# 02_-_MCU.net
KiCad netlist of a schematic drawn in Altium Designer
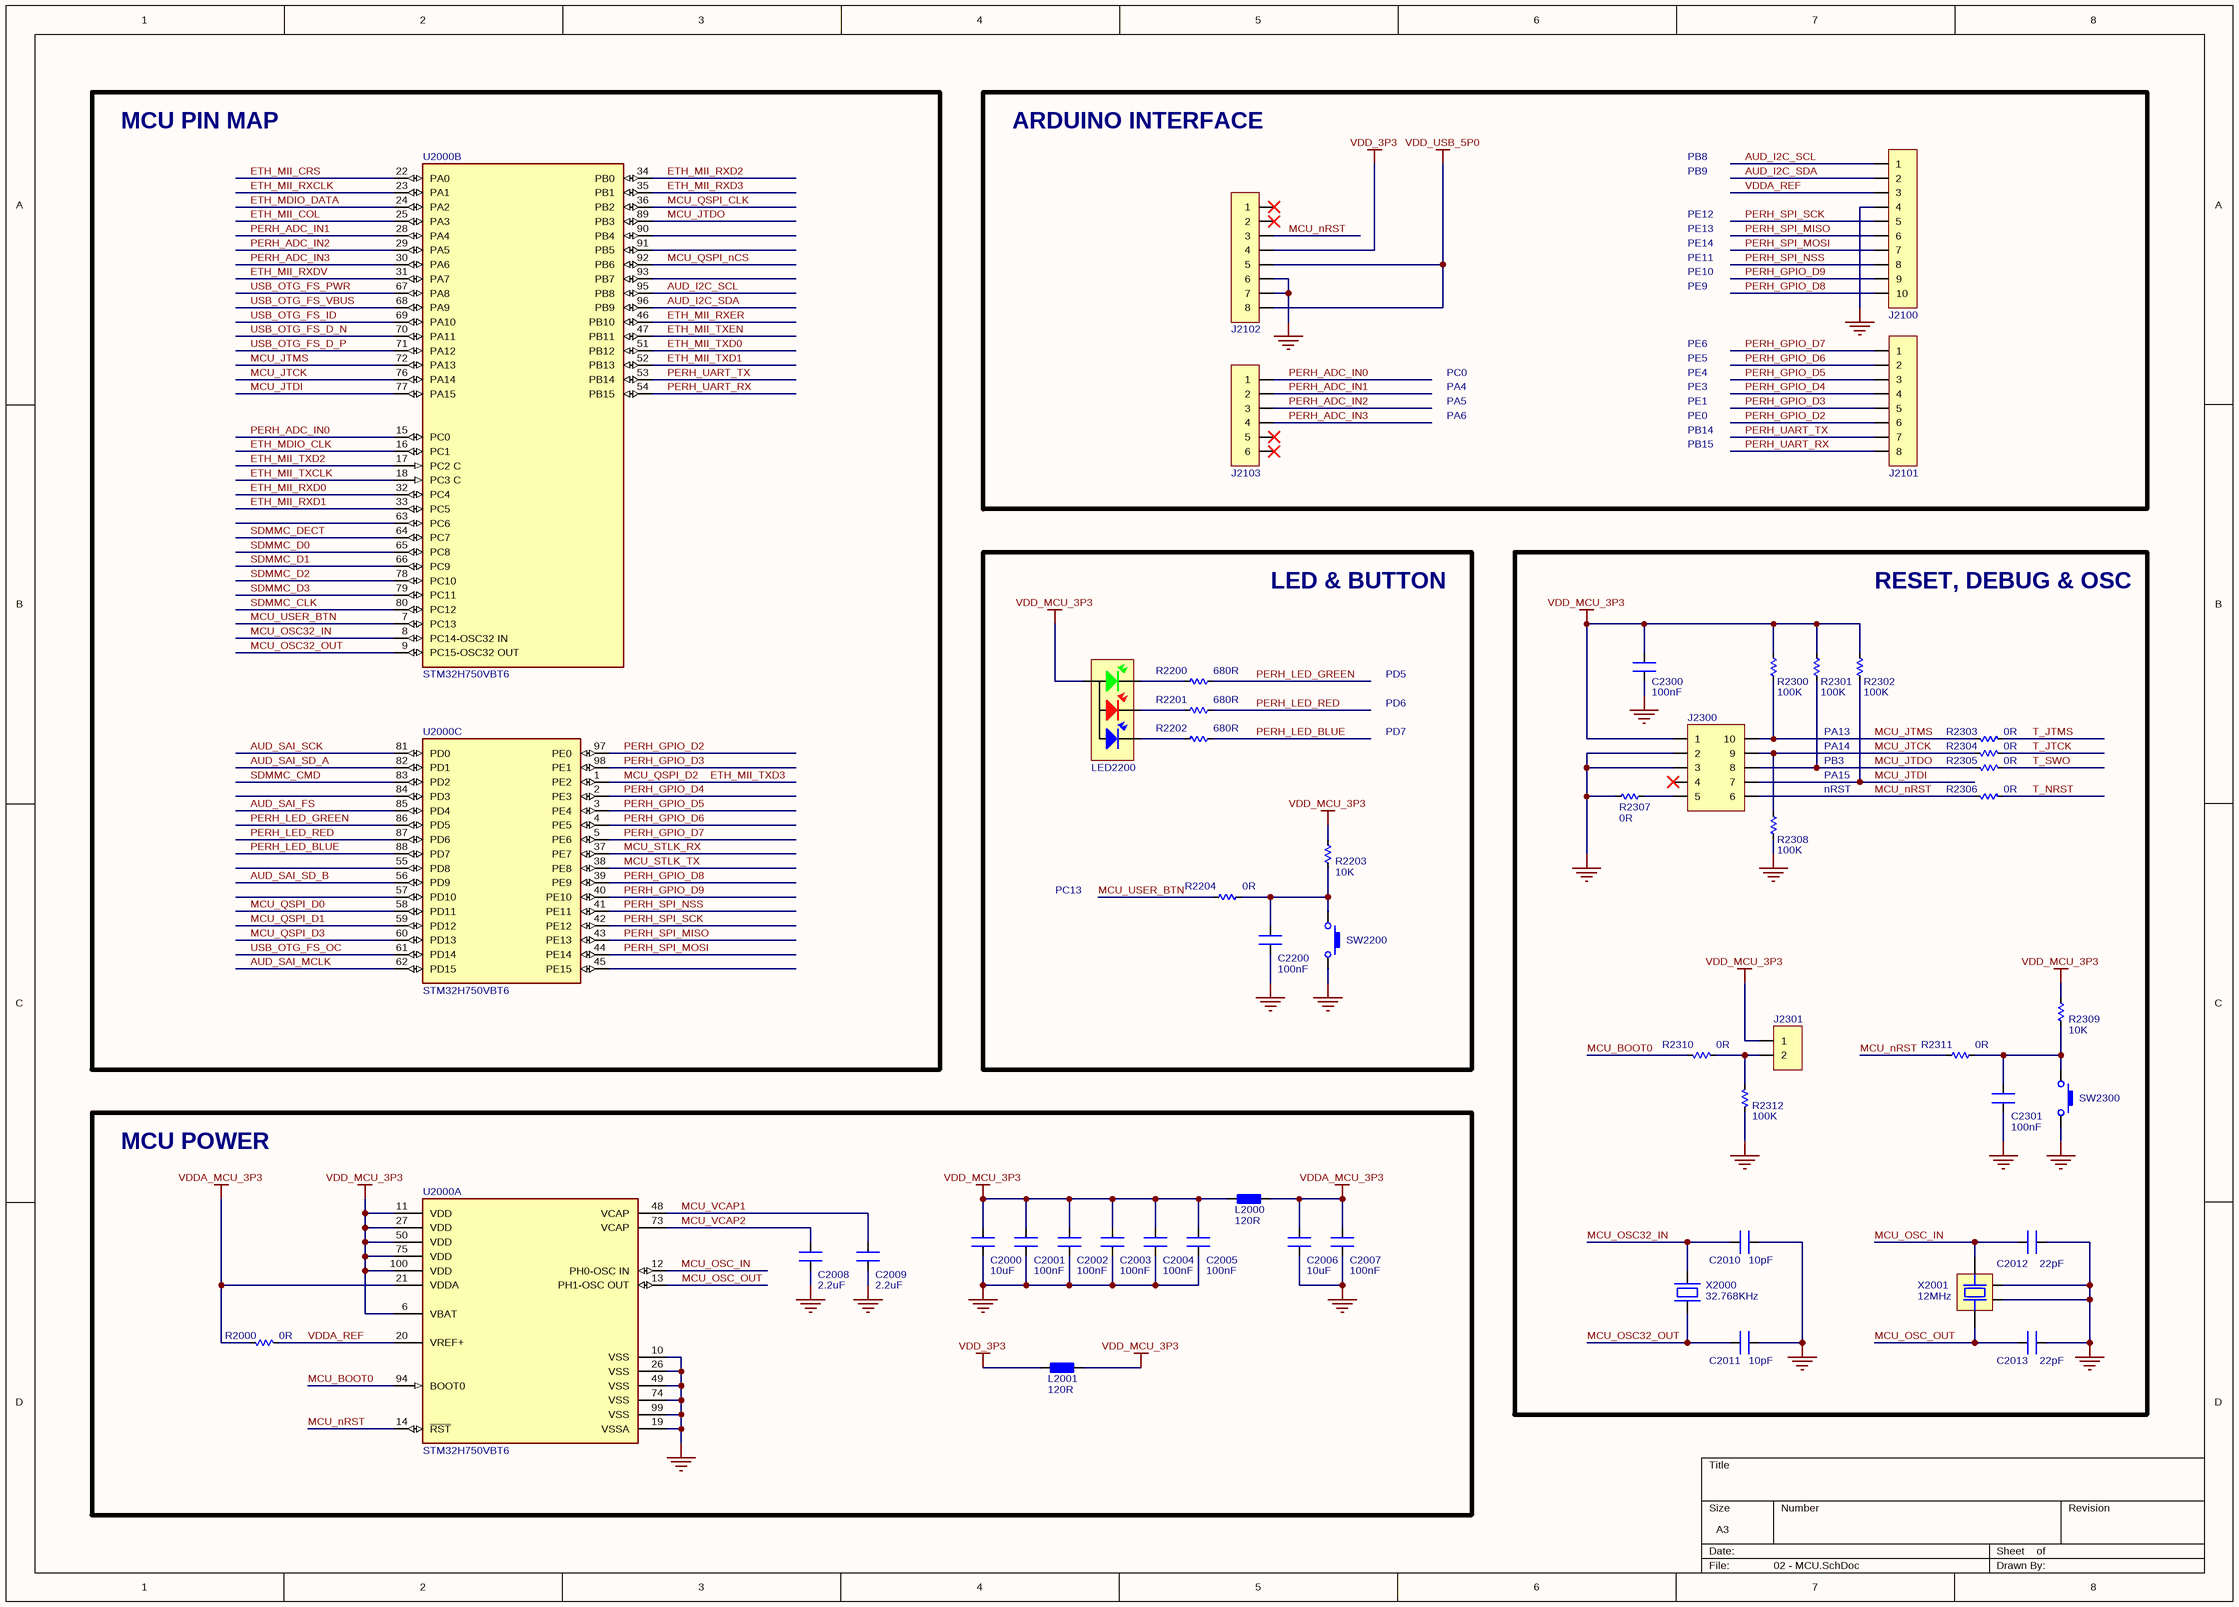
[diagram p0: 02 - MCU.SchDoc]

(export (version "E")
  (design (tool "Eeschema 10.0.6"))
  (components
    (comp (ref "C2000")
      (value "10uF")
      (footprint "CN-SMD-0603")
      (description "Ceramic Capacitor SMD 0603 10uF ±20% 10V")
      (fields (field (name "Comment") "Capacitor"))
      (libsource (lib "AS50") (part "Cap"))
    )
    (comp (ref "C2001")
      (value "100nF")
      (footprint "CN-SMD-0402")
      (description "Ceramic Capacitor SMD 0402 100nF ±20% 16V")
      (fields (field (name "Comment") "Capacitor"))
      (libsource (lib "AS50") (part "Cap"))
    )
    (comp (ref "C2002")
      (value "100nF")
      (footprint "CN-SMD-0402")
      (description "Ceramic Capacitor SMD 0402 100nF ±20% 16V")
      (fields (field (name "Comment") "Capacitor"))
      (libsource (lib "AS50") (part "Cap"))
    )
    (comp (ref "C2003")
      (value "100nF")
      (footprint "CN-SMD-0402")
      (description "Ceramic Capacitor SMD 0402 100nF ±20% 16V")
      (fields (field (name "Comment") "Capacitor"))
      (libsource (lib "AS50") (part "Cap"))
    )
    (comp (ref "C2004")
      (value "100nF")
      (footprint "CN-SMD-0402")
      (description "Ceramic Capacitor SMD 0402 100nF ±20% 16V")
      (fields (field (name "Comment") "Capacitor"))
      (libsource (lib "AS50") (part "Cap"))
    )
    (comp (ref "C2005")
      (value "100nF")
      (footprint "CN-SMD-0402")
      (description "Ceramic Capacitor SMD 0402 100nF ±20% 16V")
      (fields (field (name "Comment") "Capacitor"))
      (libsource (lib "AS50") (part "Cap"))
    )
    (comp (ref "C2006")
      (value "10uF")
      (footprint "CN-SMD-0603")
      (description "Ceramic Capacitor SMD 0603 10uF ±20% 10V")
      (fields (field (name "Comment") "Capacitor"))
      (libsource (lib "AS50") (part "Cap"))
    )
    (comp (ref "C2007")
      (value "100nF")
      (footprint "CN-SMD-0402")
      (description "Ceramic Capacitor SMD 0402 100nF ±20% 16V")
      (fields (field (name "Comment") "Capacitor"))
      (libsource (lib "AS50") (part "Cap"))
    )
    (comp (ref "C2008")
      (value "2.2uF")
      (footprint "CN-SMD-0603")
      (description "Ceramic Capacitor SMD 0603 2.2uF ±20% 16V")
      (fields (field (name "Comment") "Capacitor"))
      (libsource (lib "AS50") (part "Cap"))
    )
    (comp (ref "C2009")
      (value "2.2uF")
      (footprint "CN-SMD-0603")
      (description "Ceramic Capacitor SMD 0603 2.2uF ±20% 16V")
      (fields (field (name "Comment") "Capacitor"))
      (libsource (lib "AS50") (part "Cap"))
    )
    (comp (ref "C2010")
      (value "10pF")
      (footprint "CN-SMD-0402")
      (description "Ceramic Capacitor SMD 0402 10pF ±20% 50V")
      (fields (field (name "Comment") "Capacitor"))
      (libsource (lib "AS50") (part "Cap"))
    )
    (comp (ref "C2011")
      (value "10pF")
      (footprint "CN-SMD-0402")
      (description "Ceramic Capacitor SMD 0402 10pF ±20% 50V")
      (fields (field (name "Comment") "Capacitor"))
      (libsource (lib "AS50") (part "Cap"))
    )
    (comp (ref "C2012")
      (value "22pF")
      (footprint "CN-SMD-0402")
      (description "Ceramic Capacitor SMD 0402 22pF ±20% 50V")
      (fields (field (name "Comment") "Capacitor"))
      (libsource (lib "AS50") (part "Cap"))
    )
    (comp (ref "C2013")
      (value "22pF")
      (footprint "CN-SMD-0402")
      (description "Ceramic Capacitor SMD 0402 22pF ±20% 50V")
      (fields (field (name "Comment") "Capacitor"))
      (libsource (lib "AS50") (part "Cap"))
    )
    (comp (ref "C2200")
      (value "100nF")
      (footprint "CN-SMD-0402")
      (description "Ceramic Capacitor SMD 0402 100nF ±20% 16V")
      (fields (field (name "Comment") "Capacitor"))
      (libsource (lib "AS50") (part "Cap"))
    )
    (comp (ref "C2300")
      (value "100nF")
      (footprint "CN-SMD-0402")
      (description "Ceramic Capacitor SMD 0402 100nF ±20% 16V")
      (fields (field (name "Comment") "Capacitor"))
      (libsource (lib "AS50") (part "Cap"))
    )
    (comp (ref "C2301")
      (value "100nF")
      (footprint "CN-SMD-0402")
      (description "Ceramic Capacitor SMD 0402 100nF ±20% 16V")
      (fields (field (name "Comment") "Capacitor"))
      (libsource (lib "AS50") (part "Cap"))
    )
    (comp (ref "J2100")
      (value "Terminal strip")
      (footprint "JP10-C1T")
      (description "Terminal strip 10-pin 1-row pitch 0.1\" (2.54mm) DIP straight")
      (libsource (lib "AS50") (part "JP10"))
    )
    (comp (ref "J2101")
      (value "Terminal strip")
      (footprint "JP8-C1T")
      (description "Terminal strip 8-pin 1-row pitch 0.1\" (2.54mm) DIP straight")
      (libsource (lib "") (part "JP8_1"))
    )
    (comp (ref "J2102")
      (value "Terminal strip")
      (footprint "JP8-C1T")
      (description "Terminal strip 8-pin 1-row pitch 0.1\" (2.54mm) DIP straight")
      (libsource (lib "AS50") (part "JP8"))
    )
    (comp (ref "J2103")
      (value "Terminal strip")
      (footprint "JP6-C1T")
      (description "Terminal strip 6-pin 1-row pitch 0.1\" (2.54mm) DIP straight")
      (libsource (lib "AS50") (part "JP6"))
    )
    (comp (ref "J2300")
      (value "Terminal strip")
      (footprint "JP1.27-10P")
      (description "Terminal strip 5-pin 2-row pitch 0.05\" (1.27mm) SMD straight")
      (libsource (lib "AS50") (part "JP5x2"))
    )
    (comp (ref "J2301")
      (value "JP2")
      (footprint "JP2-D1T")
      (description "Single 2-pin jumper")
      (libsource (lib "AS50") (part "JP2"))
    )
    (comp (ref "L2000")
      (value "120R")
      (footprint "L-SMD-0402")
      (description "Ferrite bead SMD 0402 120 Ohm @100MHz")
      (fields (field (name "Comment") "Ferrite bead"))
      (libsource (lib "AS50") (part "Ferrite bead"))
    )
    (comp (ref "L2001")
      (value "120R")
      (footprint "L-SMD-0603")
      (description "Ferrite bead SMD 0603 120 Ohm @100MHz")
      (fields (field (name "Comment") "Ferrite bead"))
      (libsource (lib "AS50") (part "Ferrite bead"))
    )
    (comp (ref "LED2200")
      (value "LED")
      (footprint "LED-SMD-3528-RGB")
      (description "LED RGB Common Anode SMD-3528")
      (libsource (lib "AS50") (part "LED RGB CA"))
    )
    (comp (ref "R2000")
      (value "0R")
      (footprint "RES-SMD-0402")
      (description "Resistor SMD 0402 0R 1% 0.063W")
      (fields (field (name "Comment") "Resistor"))
      (libsource (lib "AS50") (part "Res"))
    )
    (comp (ref "R2200")
      (value "680R")
      (footprint "RES-SMD-0402")
      (description "Resistor SMD 0402 680R 1% 0.063W")
      (fields (field (name "Comment") "Resistor"))
      (libsource (lib "AS50") (part "Res"))
    )
    (comp (ref "R2201")
      (value "680R")
      (footprint "RES-SMD-0402")
      (description "Resistor SMD 0402 680R 1% 0.063W")
      (fields (field (name "Comment") "Resistor"))
      (libsource (lib "AS50") (part "Res"))
    )
    (comp (ref "R2202")
      (value "680R")
      (footprint "RES-SMD-0402")
      (description "Resistor SMD 0402 680R 1% 0.063W")
      (fields (field (name "Comment") "Resistor"))
      (libsource (lib "AS50") (part "Res"))
    )
    (comp (ref "R2203")
      (value "10K")
      (footprint "RES-SMD-0402")
      (description "Resistor SMD 0402 10K 1% 0.063W")
      (fields (field (name "Comment") "Resistor"))
      (libsource (lib "AS50") (part "Res"))
    )
    (comp (ref "R2204")
      (value "0R")
      (footprint "RES-SMD-0402")
      (description "Resistor SMD 0402 0R 1% 0.063W")
      (fields (field (name "Comment") "Resistor"))
      (libsource (lib "AS50") (part "Res"))
    )
    (comp (ref "R2300")
      (value "100K")
      (footprint "RES-SMD-0402")
      (description "Resistor SMD 0402 100K 1% 0.063W")
      (fields (field (name "Comment") "Resistor"))
      (libsource (lib "AS50") (part "Res"))
    )
    (comp (ref "R2301")
      (value "100K")
      (footprint "RES-SMD-0402")
      (description "Resistor SMD 0402 100K 1% 0.063W")
      (fields (field (name "Comment") "Resistor"))
      (libsource (lib "AS50") (part "Res"))
    )
    (comp (ref "R2302")
      (value "100K")
      (footprint "RES-SMD-0402")
      (description "Resistor SMD 0402 100K 1% 0.063W")
      (fields (field (name "Comment") "Resistor"))
      (libsource (lib "AS50") (part "Res"))
    )
    (comp (ref "R2303")
      (value "0R")
      (footprint "RES-SMD-0402")
      (description "Resistor SMD 0402 0R 1% 0.063W")
      (fields (field (name "Comment") "Resistor"))
      (libsource (lib "AS50") (part "Res"))
    )
    (comp (ref "R2304")
      (value "0R")
      (footprint "RES-SMD-0402")
      (description "Resistor SMD 0402 0R 1% 0.063W")
      (fields (field (name "Comment") "Resistor"))
      (libsource (lib "AS50") (part "Res"))
    )
    (comp (ref "R2305")
      (value "0R")
      (footprint "RES-SMD-0402")
      (description "Resistor SMD 0402 0R 1% 0.063W")
      (fields (field (name "Comment") "Resistor"))
      (libsource (lib "AS50") (part "Res"))
    )
    (comp (ref "R2306")
      (value "0R")
      (footprint "RES-SMD-0402")
      (description "Resistor SMD 0402 0R 1% 0.063W")
      (fields (field (name "Comment") "Resistor"))
      (libsource (lib "AS50") (part "Res"))
    )
    (comp (ref "R2307")
      (value "0R")
      (footprint "RES-SMD-0402")
      (description "Resistor SMD 0402 0R 1% 0.063W")
      (fields (field (name "Comment") "Resistor"))
      (libsource (lib "AS50") (part "Res"))
    )
    (comp (ref "R2308")
      (value "100K")
      (footprint "RES-SMD-0402")
      (description "Resistor SMD 0402 100K 1% 0.063W")
      (fields (field (name "Comment") "Resistor"))
      (libsource (lib "AS50") (part "Res"))
    )
    (comp (ref "R2309")
      (value "10K")
      (footprint "RES-SMD-0402")
      (description "Resistor SMD 0402 10K 1% 0.063W")
      (fields (field (name "Comment") "Resistor"))
      (libsource (lib "AS50") (part "Res"))
    )
    (comp (ref "R2310")
      (value "0R")
      (footprint "RES-SMD-0402")
      (description "Resistor SMD 0402 0R 1% 0.063W")
      (fields (field (name "Comment") "Resistor"))
      (libsource (lib "AS50") (part "Res"))
    )
    (comp (ref "R2311")
      (value "0R")
      (footprint "RES-SMD-0402")
      (description "Resistor SMD 0402 0R 1% 0.063W")
      (fields (field (name "Comment") "Resistor"))
      (libsource (lib "AS50") (part "Res"))
    )
    (comp (ref "R2312")
      (value "100K")
      (footprint "RES-SMD-0402")
      (description "Resistor SMD 0402 100K 1% 0.063W")
      (fields (field (name "Comment") "Resistor"))
      (libsource (lib "AS50") (part "Res"))
    )
    (comp (ref "SW2200")
      (value "Switch")
      (footprint "SW2-SMD-3x4x2M")
      (description "Tackle Switch 2-pin SMD 3x4x2mm")
      (libsource (lib "AS50") (part "SW2"))
    )
    (comp (ref "SW2300")
      (value "Switch")
      (footprint "SW2-SMD-3x4x2M")
      (description "Tackle Switch 2-pin SMD 3x4x2mm")
      (libsource (lib "AS50") (part "SW2"))
    )
    (comp (ref "U2000")
      (value "STM32H750VBT6")
      (footprint "FP-LQFP100-1L-IPC_B")
      (fields
        (field (name "OCTOPART") "https://octopart.com/stm32h750vbt6-stmicroelectronics-94048547")
        (field (name "MANUFACTURER") "STMicroelectronics")
      )
      (libsource (lib "Altium Content Vault") (part "aca449acb2b80670ba40d015d68dc7a"))
    )
    (comp (ref "X2000")
      (value "32.768KHz")
      (footprint "XT-SMD-FC-135")
      (description "Crystal Oscillator FC-135 32.768KHz 2-pin")
      (fields (field (name "Comment") "Crystal"))
      (libsource (lib "AS50") (part "XT2"))
    )
    (comp (ref "X2001")
      (value "12MHz")
      (footprint "XT-SMD-3225-4P")
      (description "Crystal Oscillator SMD-3225 12MHz 4-pin")
      (fields (field (name "Comment") "Crystal"))
      (libsource (lib "AS50") (part "XT4"))
    )
  )
  (nets
    (net (code "1") (name "/AUD_I2C_SCL") (class "Default")
      (node (ref "J2100") (pin "1") (pinfunction "1_1") (pintype "passive"))
      (node (ref "U2000") (pin "95") (pinfunction "PB8_95") (pintype "bidirectional"))
    )
    (net (code "2") (name "/AUD_I2C_SDA") (class "Default")
      (node (ref "J2100") (pin "2") (pinfunction "2_2") (pintype "passive"))
      (node (ref "U2000") (pin "96") (pinfunction "PB9_96") (pintype "bidirectional"))
    )
    (net (code "3") (name "/AUD_SAI_FS") (class "Default")
      (node (ref "U2000") (pin "85") (pinfunction "PD4_85") (pintype "bidirectional"))
    )
    (net (code "4") (name "/AUD_SAI_MCLK") (class "Default")
      (node (ref "U2000") (pin "62") (pinfunction "PD15_62") (pintype "bidirectional"))
    )
    (net (code "5") (name "/AUD_SAI_SCK") (class "Default")
      (node (ref "U2000") (pin "81") (pinfunction "PD0_81") (pintype "bidirectional"))
    )
    (net (code "6") (name "/AUD_SAI_SD_A") (class "Default")
      (node (ref "U2000") (pin "82") (pinfunction "PD1_82") (pintype "bidirectional"))
    )
    (net (code "7") (name "/AUD_SAI_SD_B") (class "Default")
      (node (ref "U2000") (pin "56") (pinfunction "PD9_56") (pintype "bidirectional"))
    )
    (net (code "8") (name "/ETH_MDIO_CLK") (class "Default")
      (node (ref "U2000") (pin "16") (pinfunction "PC1_16") (pintype "bidirectional"))
    )
    (net (code "9") (name "/ETH_MDIO_DATA") (class "Default")
      (node (ref "U2000") (pin "24") (pinfunction "PA2_24") (pintype "bidirectional"))
    )
    (net (code "10") (name "/ETH_MII_COL") (class "Default")
      (node (ref "U2000") (pin "25") (pinfunction "PA3_25") (pintype "bidirectional"))
    )
    (net (code "11") (name "/ETH_MII_CRS") (class "Default")
      (node (ref "U2000") (pin "22") (pinfunction "PA0_22") (pintype "bidirectional"))
    )
    (net (code "12") (name "/ETH_MII_RXCLK") (class "Default")
      (node (ref "U2000") (pin "23") (pinfunction "PA1_23") (pintype "bidirectional"))
    )
    (net (code "13") (name "/ETH_MII_RXD0") (class "Default")
      (node (ref "U2000") (pin "32") (pinfunction "PC4_32") (pintype "bidirectional"))
    )
    (net (code "14") (name "/ETH_MII_RXD1") (class "Default")
      (node (ref "U2000") (pin "33") (pinfunction "PC5_33") (pintype "bidirectional"))
    )
    (net (code "15") (name "/ETH_MII_RXD2") (class "Default")
      (node (ref "U2000") (pin "34") (pinfunction "PB0_34") (pintype "bidirectional"))
    )
    (net (code "16") (name "/ETH_MII_RXD3") (class "Default")
      (node (ref "U2000") (pin "35") (pinfunction "PB1_35") (pintype "bidirectional"))
    )
    (net (code "17") (name "/ETH_MII_RXDV") (class "Default")
      (node (ref "U2000") (pin "31") (pinfunction "PA7_31") (pintype "bidirectional"))
    )
    (net (code "18") (name "/ETH_MII_RXER") (class "Default")
      (node (ref "U2000") (pin "46") (pinfunction "PB10_46") (pintype "bidirectional"))
    )
    (net (code "19") (name "/ETH_MII_TXCLK") (class "Default")
      (node (ref "U2000") (pin "18") (pinfunction "PC3_C_18") (pintype "input"))
    )
    (net (code "20") (name "/ETH_MII_TXD0") (class "Default")
      (node (ref "U2000") (pin "51") (pinfunction "PB12_51") (pintype "bidirectional"))
    )
    (net (code "21") (name "/ETH_MII_TXD1") (class "Default")
      (node (ref "U2000") (pin "52") (pinfunction "PB13_52") (pintype "bidirectional"))
    )
    (net (code "22") (name "/ETH_MII_TXD2") (class "Default")
      (node (ref "U2000") (pin "17") (pinfunction "PC2_C_17") (pintype "input"))
    )
    (net (code "23") (name "/ETH_MII_TXD3") (class "Default")
      (node (ref "U2000") (pin "1") (pinfunction "PE2_1") (pintype "bidirectional"))
    )
    (net (code "24") (name "/ETH_MII_TXEN") (class "Default")
      (node (ref "U2000") (pin "47") (pinfunction "PB11_47") (pintype "bidirectional"))
    )
    (net (code "25") (name "/MCU_BOOT0") (class "Default")
      (node (ref "R2310") (pin "2") (pinfunction "2_2") (pintype "passive"))
      (node (ref "U2000") (pin "94") (pinfunction "BOOT0_94") (pintype "input"))
    )
    (net (code "26") (name "/MCU_JTCK") (class "Default")
      (node (ref "J2300") (pin "9") (pinfunction "9_9") (pintype "passive"))
      (node (ref "R2304") (pin "2") (pinfunction "2_2") (pintype "passive"))
      (node (ref "R2308") (pin "1") (pinfunction "1_1") (pintype "passive"))
      (node (ref "U2000") (pin "76") (pinfunction "PA14_76") (pintype "bidirectional"))
    )
    (net (code "27") (name "/MCU_JTDI") (class "Default")
      (node (ref "J2300") (pin "7") (pinfunction "7_7") (pintype "passive"))
      (node (ref "R2302") (pin "2") (pinfunction "2_2") (pintype "passive"))
      (node (ref "U2000") (pin "77") (pinfunction "PA15_77") (pintype "bidirectional"))
    )
    (net (code "28") (name "/MCU_JTDO") (class "Default")
      (node (ref "J2300") (pin "8") (pinfunction "8_8") (pintype "passive"))
      (node (ref "R2301") (pin "2") (pinfunction "2_2") (pintype "passive"))
      (node (ref "R2305") (pin "2") (pinfunction "2_2") (pintype "passive"))
      (node (ref "U2000") (pin "89") (pinfunction "PB3_89") (pintype "bidirectional"))
    )
    (net (code "29") (name "/MCU_JTMS") (class "Default")
      (node (ref "J2300") (pin "10") (pinfunction "10_10") (pintype "passive"))
      (node (ref "R2300") (pin "2") (pinfunction "2_2") (pintype "passive"))
      (node (ref "R2303") (pin "2") (pinfunction "2_2") (pintype "passive"))
      (node (ref "U2000") (pin "72") (pinfunction "PA13_72") (pintype "bidirectional"))
    )
    (net (code "30") (name "/MCU_OSC32_IN") (class "Default")
      (node (ref "C2010") (pin "2") (pinfunction "2_2") (pintype "passive"))
      (node (ref "U2000") (pin "8") (pinfunction "PC14-OSC32_IN_8") (pintype "bidirectional"))
      (node (ref "X2000") (pin "2") (pinfunction "2_2") (pintype "passive"))
    )
    (net (code "31") (name "/MCU_OSC32_OUT") (class "Default")
      (node (ref "C2011") (pin "2") (pinfunction "2_2") (pintype "passive"))
      (node (ref "U2000") (pin "9") (pinfunction "PC15-OSC32_OUT_9") (pintype "bidirectional"))
      (node (ref "X2000") (pin "1") (pinfunction "1_1") (pintype "passive"))
    )
    (net (code "32") (name "/MCU_OSC_IN") (class "Default")
      (node (ref "C2012") (pin "1") (pinfunction "1_1") (pintype "passive"))
      (node (ref "U2000") (pin "12") (pinfunction "PH0-OSC_IN_12") (pintype "bidirectional"))
      (node (ref "X2001") (pin "3") (pinfunction "3_3") (pintype "passive"))
    )
    (net (code "33") (name "/MCU_OSC_OUT") (class "Default")
      (node (ref "C2013") (pin "1") (pinfunction "1_1") (pintype "passive"))
      (node (ref "U2000") (pin "13") (pinfunction "PH1-OSC_OUT_13") (pintype "bidirectional"))
      (node (ref "X2001") (pin "1") (pinfunction "1_1") (pintype "passive"))
    )
    (net (code "34") (name "/MCU_QSPI_CLK") (class "Default")
      (node (ref "U2000") (pin "36") (pinfunction "PB2_36") (pintype "bidirectional"))
    )
    (net (code "35") (name "/MCU_QSPI_D0") (class "Default")
      (node (ref "U2000") (pin "58") (pinfunction "PD11_58") (pintype "bidirectional"))
    )
    (net (code "36") (name "/MCU_QSPI_D1") (class "Default")
      (node (ref "U2000") (pin "59") (pinfunction "PD12_59") (pintype "bidirectional"))
    )
    (net (code "37") (name "/MCU_QSPI_D3") (class "Default")
      (node (ref "U2000") (pin "60") (pinfunction "PD13_60") (pintype "bidirectional"))
    )
    (net (code "38") (name "/MCU_QSPI_nCS") (class "Default")
      (node (ref "U2000") (pin "92") (pinfunction "PB6_92") (pintype "bidirectional"))
    )
    (net (code "39") (name "/MCU_STLK_RX") (class "Default")
      (node (ref "U2000") (pin "37") (pinfunction "PE7_37") (pintype "bidirectional"))
    )
    (net (code "40") (name "/MCU_STLK_TX") (class "Default")
      (node (ref "U2000") (pin "38") (pinfunction "PE8_38") (pintype "bidirectional"))
    )
    (net (code "41") (name "/MCU_USER_BTN") (class "Default")
      (node (ref "R2204") (pin "1") (pinfunction "1_1") (pintype "passive"))
      (node (ref "U2000") (pin "7") (pinfunction "PC13_7") (pintype "bidirectional"))
    )
    (net (code "42") (name "/MCU_VCAP1") (class "Default")
      (node (ref "C2009") (pin "2") (pinfunction "2_2") (pintype "passive"))
      (node (ref "U2000") (pin "48") (pinfunction "VCAP_48") (pintype "power_in"))
    )
    (net (code "43") (name "/MCU_VCAP2") (class "Default")
      (node (ref "C2008") (pin "2") (pinfunction "2_2") (pintype "passive"))
      (node (ref "U2000") (pin "73") (pinfunction "VCAP_73") (pintype "power_in"))
    )
    (net (code "44") (name "/MCU_nRST") (class "Default")
      (node (ref "J2102") (pin "3") (pinfunction "3_3") (pintype "passive"))
      (node (ref "J2300") (pin "6") (pinfunction "6_6") (pintype "passive"))
      (node (ref "R2306") (pin "2") (pinfunction "2_2") (pintype "passive"))
      (node (ref "R2311") (pin "1") (pinfunction "1_1") (pintype "passive"))
      (node (ref "U2000") (pin "14") (pinfunction "~{RST}_14") (pintype "bidirectional"))
    )
    (net (code "45") (name "/PERH_ADC_IN0") (class "Default")
      (node (ref "J2103") (pin "1") (pinfunction "1_1") (pintype "passive"))
      (node (ref "U2000") (pin "15") (pinfunction "PC0_15") (pintype "bidirectional"))
    )
    (net (code "46") (name "/PERH_ADC_IN1") (class "Default")
      (node (ref "J2103") (pin "2") (pinfunction "2_2") (pintype "passive"))
      (node (ref "U2000") (pin "28") (pinfunction "PA4_28") (pintype "bidirectional"))
    )
    (net (code "47") (name "/PERH_ADC_IN2") (class "Default")
      (node (ref "J2103") (pin "3") (pinfunction "3_3") (pintype "passive"))
      (node (ref "U2000") (pin "29") (pinfunction "PA5_29") (pintype "bidirectional"))
    )
    (net (code "48") (name "/PERH_ADC_IN3") (class "Default")
      (node (ref "J2103") (pin "4") (pinfunction "4_4") (pintype "passive"))
      (node (ref "U2000") (pin "30") (pinfunction "PA6_30") (pintype "bidirectional"))
    )
    (net (code "49") (name "/PERH_GPIO_D2") (class "Default")
      (node (ref "J2101") (pin "6") (pinfunction "6_6") (pintype "passive"))
      (node (ref "U2000") (pin "97") (pinfunction "PE0_97") (pintype "bidirectional"))
    )
    (net (code "50") (name "/PERH_GPIO_D3") (class "Default")
      (node (ref "J2101") (pin "5") (pinfunction "5_5") (pintype "passive"))
      (node (ref "U2000") (pin "98") (pinfunction "PE1_98") (pintype "bidirectional"))
    )
    (net (code "51") (name "/PERH_GPIO_D4") (class "Default")
      (node (ref "J2101") (pin "4") (pinfunction "4_4") (pintype "passive"))
      (node (ref "U2000") (pin "2") (pinfunction "PE3_2") (pintype "bidirectional"))
    )
    (net (code "52") (name "/PERH_GPIO_D5") (class "Default")
      (node (ref "J2101") (pin "3") (pinfunction "3_3") (pintype "passive"))
      (node (ref "U2000") (pin "3") (pinfunction "PE4_3") (pintype "bidirectional"))
    )
    (net (code "53") (name "/PERH_GPIO_D6") (class "Default")
      (node (ref "J2101") (pin "2") (pinfunction "2_2") (pintype "passive"))
      (node (ref "U2000") (pin "4") (pinfunction "PE5_4") (pintype "bidirectional"))
    )
    (net (code "54") (name "/PERH_GPIO_D7") (class "Default")
      (node (ref "J2101") (pin "1") (pinfunction "1_1") (pintype "passive"))
      (node (ref "U2000") (pin "5") (pinfunction "PE6_5") (pintype "bidirectional"))
    )
    (net (code "55") (name "/PERH_GPIO_D8") (class "Default")
      (node (ref "J2100") (pin "10") (pinfunction "10_10") (pintype "passive"))
      (node (ref "U2000") (pin "39") (pinfunction "PE9_39") (pintype "bidirectional"))
    )
    (net (code "56") (name "/PERH_GPIO_D9") (class "Default")
      (node (ref "J2100") (pin "9") (pinfunction "9_9") (pintype "passive"))
      (node (ref "U2000") (pin "40") (pinfunction "PE10_40") (pintype "bidirectional"))
    )
    (net (code "57") (name "/PERH_LED_BLUE") (class "Default")
      (node (ref "R2202") (pin "2") (pinfunction "2_2") (pintype "passive"))
      (node (ref "U2000") (pin "88") (pinfunction "PD7_88") (pintype "bidirectional"))
    )
    (net (code "58") (name "/PERH_LED_GREEN") (class "Default")
      (node (ref "R2200") (pin "2") (pinfunction "2_2") (pintype "passive"))
      (node (ref "U2000") (pin "86") (pinfunction "PD5_86") (pintype "bidirectional"))
    )
    (net (code "59") (name "/PERH_LED_RED") (class "Default")
      (node (ref "R2201") (pin "2") (pinfunction "2_2") (pintype "passive"))
      (node (ref "U2000") (pin "87") (pinfunction "PD6_87") (pintype "bidirectional"))
    )
    (net (code "60") (name "/PERH_SPI_MISO") (class "Default")
      (node (ref "J2100") (pin "6") (pinfunction "6_6") (pintype "passive"))
      (node (ref "U2000") (pin "43") (pinfunction "PE13_43") (pintype "bidirectional"))
    )
    (net (code "61") (name "/PERH_SPI_MOSI") (class "Default")
      (node (ref "J2100") (pin "7") (pinfunction "7_7") (pintype "passive"))
      (node (ref "U2000") (pin "44") (pinfunction "PE14_44") (pintype "bidirectional"))
    )
    (net (code "62") (name "/PERH_SPI_NSS") (class "Default")
      (node (ref "J2100") (pin "8") (pinfunction "8_8") (pintype "passive"))
      (node (ref "U2000") (pin "41") (pinfunction "PE11_41") (pintype "bidirectional"))
    )
    (net (code "63") (name "/PERH_SPI_SCK") (class "Default")
      (node (ref "J2100") (pin "5") (pinfunction "5_5") (pintype "passive"))
      (node (ref "U2000") (pin "42") (pinfunction "PE12_42") (pintype "bidirectional"))
    )
    (net (code "64") (name "/PERH_UART_RX") (class "Default")
      (node (ref "J2101") (pin "8") (pinfunction "8_8") (pintype "passive"))
      (node (ref "U2000") (pin "54") (pinfunction "PB15_54") (pintype "bidirectional"))
    )
    (net (code "65") (name "/PERH_UART_TX") (class "Default")
      (node (ref "J2101") (pin "7") (pinfunction "7_7") (pintype "passive"))
      (node (ref "U2000") (pin "53") (pinfunction "PB14_53") (pintype "bidirectional"))
    )
    (net (code "66") (name "/SDMMC_CLK") (class "Default")
      (node (ref "U2000") (pin "80") (pinfunction "PC12_80") (pintype "bidirectional"))
    )
    (net (code "67") (name "/SDMMC_CMD") (class "Default")
      (node (ref "U2000") (pin "83") (pinfunction "PD2_83") (pintype "bidirectional"))
    )
    (net (code "68") (name "/SDMMC_D0") (class "Default")
      (node (ref "U2000") (pin "65") (pinfunction "PC8_65") (pintype "bidirectional"))
    )
    (net (code "69") (name "/SDMMC_D1") (class "Default")
      (node (ref "U2000") (pin "66") (pinfunction "PC9_66") (pintype "bidirectional"))
    )
    (net (code "70") (name "/SDMMC_D2") (class "Default")
      (node (ref "U2000") (pin "78") (pinfunction "PC10_78") (pintype "bidirectional"))
    )
    (net (code "71") (name "/SDMMC_D3") (class "Default")
      (node (ref "U2000") (pin "79") (pinfunction "PC11_79") (pintype "bidirectional"))
    )
    (net (code "72") (name "/SDMMC_DECT") (class "Default")
      (node (ref "U2000") (pin "64") (pinfunction "PC7_64") (pintype "bidirectional"))
    )
    (net (code "73") (name "/T_JTCK") (class "Default")
      (node (ref "R2304") (pin "1") (pinfunction "1_1") (pintype "passive"))
    )
    (net (code "74") (name "/T_JTMS") (class "Default")
      (node (ref "R2303") (pin "1") (pinfunction "1_1") (pintype "passive"))
    )
    (net (code "75") (name "/T_NRST") (class "Default")
      (node (ref "R2306") (pin "1") (pinfunction "1_1") (pintype "passive"))
    )
    (net (code "76") (name "/T_SWO") (class "Default")
      (node (ref "R2305") (pin "1") (pinfunction "1_1") (pintype "passive"))
    )
    (net (code "77") (name "/USB_OTG_FS_D_N") (class "Default")
      (node (ref "U2000") (pin "70") (pinfunction "PA11_70") (pintype "bidirectional"))
    )
    (net (code "78") (name "/USB_OTG_FS_D_P") (class "Default")
      (node (ref "U2000") (pin "71") (pinfunction "PA12_71") (pintype "bidirectional"))
    )
    (net (code "79") (name "/USB_OTG_FS_ID") (class "Default")
      (node (ref "U2000") (pin "69") (pinfunction "PA10_69") (pintype "bidirectional"))
    )
    (net (code "80") (name "/USB_OTG_FS_OC") (class "Default")
      (node (ref "U2000") (pin "61") (pinfunction "PD14_61") (pintype "bidirectional"))
    )
    (net (code "81") (name "/USB_OTG_FS_PWR") (class "Default")
      (node (ref "U2000") (pin "67") (pinfunction "PA8_67") (pintype "bidirectional"))
    )
    (net (code "82") (name "/USB_OTG_FS_VBUS") (class "Default")
      (node (ref "U2000") (pin "68") (pinfunction "PA9_68") (pintype "bidirectional"))
    )
    (net (code "83") (name "/VDDA_REF") (class "Default")
      (node (ref "J2100") (pin "3") (pinfunction "3_3") (pintype "passive"))
      (node (ref "R2000") (pin "1") (pinfunction "1_1") (pintype "passive"))
      (node (ref "U2000") (pin "20") (pinfunction "VREF+_20") (pintype "power_in"))
    )
    (net (code "84") (name "GND") (class "Default")
      (node (ref "C2000") (pin "1") (pinfunction "1_1") (pintype "passive"))
      (node (ref "C2001") (pin "1") (pinfunction "1_1") (pintype "passive"))
      (node (ref "C2002") (pin "1") (pinfunction "1_1") (pintype "passive"))
      (node (ref "C2003") (pin "1") (pinfunction "1_1") (pintype "passive"))
      (node (ref "C2004") (pin "1") (pinfunction "1_1") (pintype "passive"))
      (node (ref "C2005") (pin "1") (pinfunction "1_1") (pintype "passive"))
      (node (ref "C2006") (pin "1") (pinfunction "1_1") (pintype "passive"))
      (node (ref "C2007") (pin "1") (pinfunction "1_1") (pintype "passive"))
      (node (ref "C2008") (pin "1") (pinfunction "1_1") (pintype "passive"))
      (node (ref "C2009") (pin "1") (pinfunction "1_1") (pintype "passive"))
      (node (ref "C2010") (pin "1") (pinfunction "1_1") (pintype "passive"))
      (node (ref "C2011") (pin "1") (pinfunction "1_1") (pintype "passive"))
      (node (ref "C2012") (pin "2") (pinfunction "2_2") (pintype "passive"))
      (node (ref "C2013") (pin "2") (pinfunction "2_2") (pintype "passive"))
      (node (ref "C2200") (pin "1") (pinfunction "1_1") (pintype "passive"))
      (node (ref "C2300") (pin "1") (pinfunction "1_1") (pintype "passive"))
      (node (ref "C2301") (pin "1") (pinfunction "1_1") (pintype "passive"))
      (node (ref "J2100") (pin "4") (pinfunction "4_4") (pintype "passive"))
      (node (ref "J2102") (pin "6") (pinfunction "6_6") (pintype "passive"))
      (node (ref "J2102") (pin "7") (pinfunction "7_7") (pintype "passive"))
      (node (ref "J2300") (pin "2") (pinfunction "2_2") (pintype "passive"))
      (node (ref "J2300") (pin "3") (pinfunction "3_3") (pintype "passive"))
      (node (ref "R2307") (pin "2") (pinfunction "2_2") (pintype "passive"))
      (node (ref "R2308") (pin "2") (pinfunction "2_2") (pintype "passive"))
      (node (ref "R2312") (pin "2") (pinfunction "2_2") (pintype "passive"))
      (node (ref "SW2200") (pin "2") (pinfunction "2_2") (pintype "passive"))
      (node (ref "SW2300") (pin "2") (pinfunction "2_2") (pintype "passive"))
      (node (ref "U2000") (pin "10") (pinfunction "VSS_10") (pintype "power_in"))
      (node (ref "U2000") (pin "19") (pinfunction "VSSA_19") (pintype "power_in"))
      (node (ref "U2000") (pin "26") (pinfunction "VSS_26") (pintype "power_in"))
      (node (ref "U2000") (pin "49") (pinfunction "VSS_49") (pintype "power_in"))
      (node (ref "U2000") (pin "74") (pinfunction "VSS_74") (pintype "power_in"))
      (node (ref "U2000") (pin "99") (pinfunction "VSS_99") (pintype "power_in"))
      (node (ref "X2001") (pin "2") (pinfunction "2_2") (pintype "power_in"))
      (node (ref "X2001") (pin "4") (pinfunction "4_4") (pintype "power_in"))
    )
    (net (code "85") (name "Net-(C2200-Pad2)") (class "Default")
      (node (ref "C2200") (pin "2") (pinfunction "2_2") (pintype "passive"))
      (node (ref "R2203") (pin "2") (pinfunction "2_2") (pintype "passive"))
      (node (ref "R2204") (pin "2") (pinfunction "2_2") (pintype "passive"))
      (node (ref "SW2200") (pin "1") (pinfunction "1_1") (pintype "passive"))
    )
    (net (code "86") (name "Net-(C2301-Pad2)") (class "Default")
      (node (ref "C2301") (pin "2") (pinfunction "2_2") (pintype "passive"))
      (node (ref "R2309") (pin "2") (pinfunction "2_2") (pintype "passive"))
      (node (ref "R2311") (pin "2") (pinfunction "2_2") (pintype "passive"))
      (node (ref "SW2300") (pin "1") (pinfunction "1_1") (pintype "passive"))
    )
    (net (code "87") (name "Net-(J2300-Pad5)") (class "Default")
      (node (ref "J2300") (pin "5") (pinfunction "5_5") (pintype "passive"))
      (node (ref "R2307") (pin "1") (pinfunction "1_1") (pintype "passive"))
    )
    (net (code "88") (name "Net-(J2301-Pad2)") (class "Default")
      (node (ref "J2301") (pin "2") (pinfunction "2_2") (pintype "passive"))
      (node (ref "R2310") (pin "1") (pinfunction "1_1") (pintype "passive"))
      (node (ref "R2312") (pin "1") (pinfunction "1_1") (pintype "passive"))
    )
    (net (code "89") (name "Net-(LED2200-Blue_Cathode)") (class "Default")
      (node (ref "LED2200") (pin "3") (pinfunction "Blue_Cathode_3") (pintype "passive"))
      (node (ref "R2202") (pin "1") (pinfunction "1_1") (pintype "passive"))
    )
    (net (code "90") (name "Net-(LED2200-Green_Cathode)") (class "Default")
      (node (ref "LED2200") (pin "4") (pinfunction "Green_Cathode_4") (pintype "passive"))
      (node (ref "R2200") (pin "1") (pinfunction "1_1") (pintype "passive"))
    )
    (net (code "91") (name "Net-(LED2200-Red_Cathode)") (class "Default")
      (node (ref "LED2200") (pin "1") (pinfunction "Red_Cathode_1") (pintype "passive"))
      (node (ref "R2201") (pin "1") (pinfunction "1_1") (pintype "passive"))
    )
    (net (code "92") (name "VDDA_MCU_3P3") (class "Default")
      (node (ref "C2006") (pin "2") (pinfunction "2_2") (pintype "passive"))
      (node (ref "C2007") (pin "2") (pinfunction "2_2") (pintype "passive"))
      (node (ref "L2000") (pin "1") (pinfunction "1_1") (pintype "passive"))
      (node (ref "R2000") (pin "2") (pinfunction "2_2") (pintype "passive"))
      (node (ref "U2000") (pin "21") (pinfunction "VDDA_21") (pintype "power_in"))
    )
    (net (code "93") (name "VDD_3P3") (class "Default")
      (node (ref "J2102") (pin "4") (pinfunction "4_4") (pintype "passive"))
      (node (ref "L2001") (pin "2") (pinfunction "2_2") (pintype "passive"))
    )
    (net (code "94") (name "VDD_MCU_3P3") (class "Default")
      (node (ref "C2000") (pin "2") (pinfunction "2_2") (pintype "passive"))
      (node (ref "C2001") (pin "2") (pinfunction "2_2") (pintype "passive"))
      (node (ref "C2002") (pin "2") (pinfunction "2_2") (pintype "passive"))
      (node (ref "C2003") (pin "2") (pinfunction "2_2") (pintype "passive"))
      (node (ref "C2004") (pin "2") (pinfunction "2_2") (pintype "passive"))
      (node (ref "C2005") (pin "2") (pinfunction "2_2") (pintype "passive"))
      (node (ref "C2300") (pin "2") (pinfunction "2_2") (pintype "passive"))
      (node (ref "J2300") (pin "1") (pinfunction "1_1") (pintype "passive"))
      (node (ref "J2301") (pin "1") (pinfunction "1_1") (pintype "passive"))
      (node (ref "L2000") (pin "2") (pinfunction "2_2") (pintype "passive"))
      (node (ref "L2001") (pin "1") (pinfunction "1_1") (pintype "passive"))
      (node (ref "LED2200") (pin "2") (pinfunction "Common_2") (pintype "passive"))
      (node (ref "R2203") (pin "1") (pinfunction "1_1") (pintype "passive"))
      (node (ref "R2300") (pin "1") (pinfunction "1_1") (pintype "passive"))
      (node (ref "R2301") (pin "1") (pinfunction "1_1") (pintype "passive"))
      (node (ref "R2302") (pin "1") (pinfunction "1_1") (pintype "passive"))
      (node (ref "R2309") (pin "1") (pinfunction "1_1") (pintype "passive"))
      (node (ref "U2000") (pin "100") (pinfunction "VDD_100") (pintype "power_in"))
      (node (ref "U2000") (pin "11") (pinfunction "VDD_11") (pintype "power_in"))
      (node (ref "U2000") (pin "27") (pinfunction "VDD_27") (pintype "power_in"))
      (node (ref "U2000") (pin "50") (pinfunction "VDD_50") (pintype "power_in"))
      (node (ref "U2000") (pin "6") (pinfunction "VBAT_6") (pintype "power_in"))
      (node (ref "U2000") (pin "75") (pinfunction "VDD_75") (pintype "power_in"))
    )
    (net (code "95") (name "VDD_USB_5P0") (class "Default")
      (node (ref "J2102") (pin "5") (pinfunction "5_5") (pintype "passive"))
      (node (ref "J2102") (pin "8") (pinfunction "8_8") (pintype "passive"))
    )
    (net (code "96") (name "unconnected-(J2102-Pad1)") (class "Default")
      (node (ref "J2102") (pin "1") (pinfunction "1_1") (pintype "passive+no_connect"))
    )
    (net (code "97") (name "unconnected-(J2102-Pad2)") (class "Default")
      (node (ref "J2102") (pin "2") (pinfunction "2_2") (pintype "passive+no_connect"))
    )
    (net (code "98") (name "unconnected-(J2103-Pad5)") (class "Default")
      (node (ref "J2103") (pin "5") (pinfunction "5_5") (pintype "passive+no_connect"))
    )
    (net (code "99") (name "unconnected-(J2103-Pad6)") (class "Default")
      (node (ref "J2103") (pin "6") (pinfunction "6_6") (pintype "passive+no_connect"))
    )
    (net (code "100") (name "unconnected-(J2300-Pad4)") (class "Default")
      (node (ref "J2300") (pin "4") (pinfunction "4_4") (pintype "passive+no_connect"))
    )
    (net (code "101") (name "unconnected-(U2000B-PB4-Pad90)") (class "Default")
      (node (ref "U2000") (pin "90") (pinfunction "PB4_90") (pintype "bidirectional"))
    )
    (net (code "102") (name "unconnected-(U2000B-PB5-Pad91)") (class "Default")
      (node (ref "U2000") (pin "91") (pinfunction "PB5_91") (pintype "bidirectional"))
    )
    (net (code "103") (name "unconnected-(U2000B-PB7-Pad93)") (class "Default")
      (node (ref "U2000") (pin "93") (pinfunction "PB7_93") (pintype "bidirectional"))
    )
    (net (code "104") (name "unconnected-(U2000B-PC6-Pad63)") (class "Default")
      (node (ref "U2000") (pin "63") (pinfunction "PC6_63") (pintype "bidirectional"))
    )
    (net (code "105") (name "unconnected-(U2000C-PD3-Pad84)") (class "Default")
      (node (ref "U2000") (pin "84") (pinfunction "PD3_84") (pintype "bidirectional"))
    )
    (net (code "106") (name "unconnected-(U2000C-PD8-Pad55)") (class "Default")
      (node (ref "U2000") (pin "55") (pinfunction "PD8_55") (pintype "bidirectional"))
    )
    (net (code "107") (name "unconnected-(U2000C-PD10-Pad57)") (class "Default")
      (node (ref "U2000") (pin "57") (pinfunction "PD10_57") (pintype "bidirectional"))
    )
    (net (code "108") (name "unconnected-(U2000C-PE15-Pad45)") (class "Default")
      (node (ref "U2000") (pin "45") (pinfunction "PE15_45") (pintype "bidirectional"))
    )
  )
)
